# MegaShield_v0_1.net
KiCad netlist of a schematic drawn in EAGLE
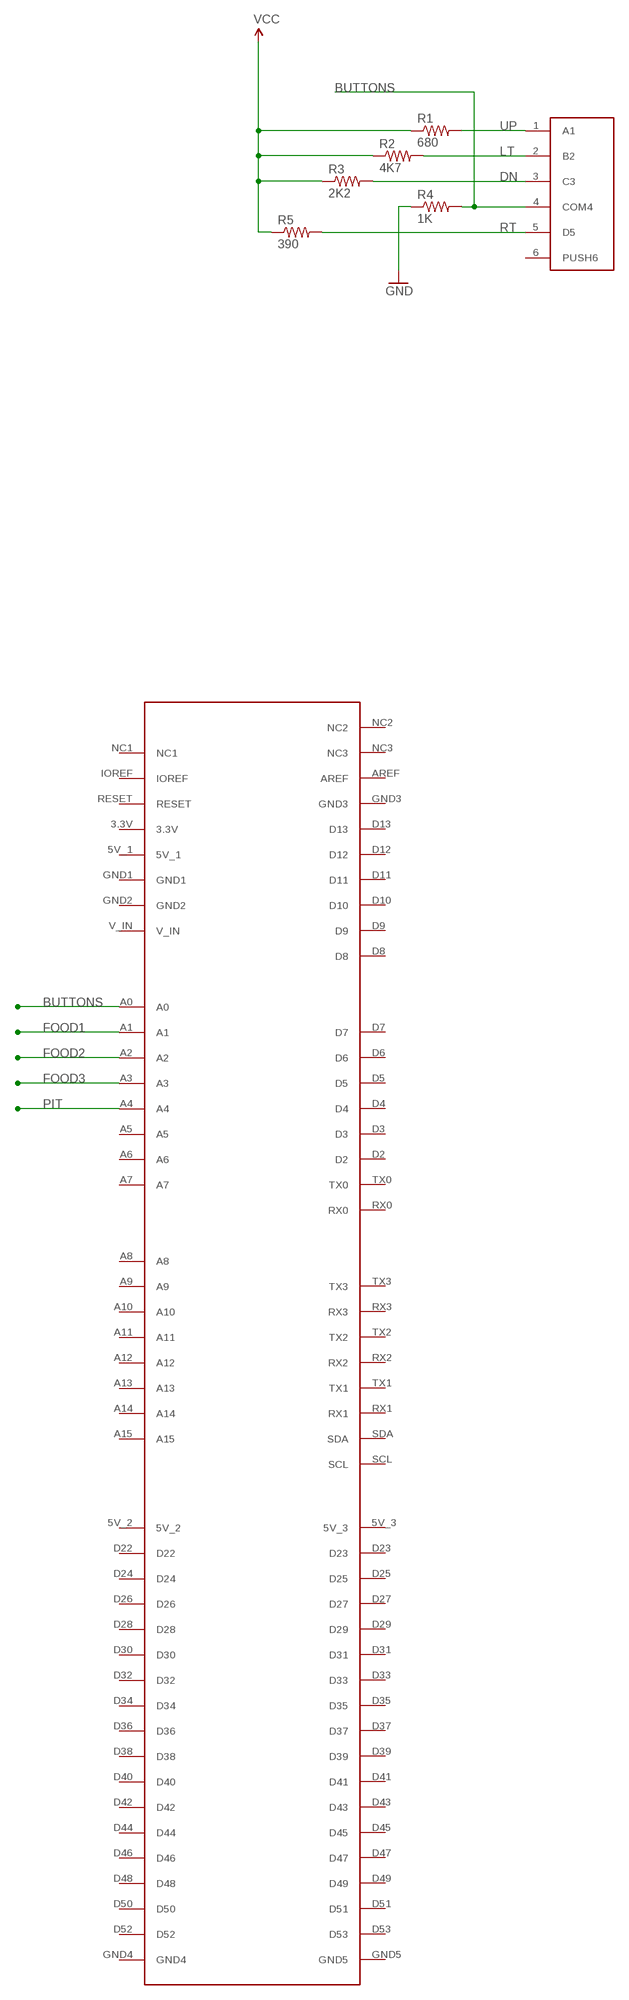
[diagram p0: schematic, sheet 1]

(export (version "E")
  (design (tool "Eeschema 10.0.6"))
  (components
    (comp (ref "R1")
      (value "680")
      (footprint "eagle-import:1206")
      (libsource (lib "eagle-import") (part "RESISTOR1206"))
    )
    (comp (ref "R2")
      (value "4K7")
      (footprint "eagle-import:1206")
      (libsource (lib "eagle-import") (part "RESISTOR1206"))
    )
    (comp (ref "R3")
      (value "2K2")
      (footprint "eagle-import:1206")
      (libsource (lib "eagle-import") (part "RESISTOR1206"))
    )
    (comp (ref "R4")
      (value "1K")
      (footprint "eagle-import:1206")
      (libsource (lib "eagle-import") (part "RESISTOR1206"))
    )
    (comp (ref "R5")
      (value "390")
      (footprint "eagle-import:1206")
      (libsource (lib "eagle-import") (part "RESISTOR1206"))
    )
    (comp (ref "U$1")
      (value "MEGASHILED")
      (footprint "eagle-import:MEGASHIELD")
      (libsource (lib "eagle-import") (part "MEGASHILED"))
    )
    (comp (ref "U$2")
      (value "SKQUAAA010")
      (footprint "eagle-import:SKQUAAA010")
      (libsource (lib "eagle-import") (part "SKQUAAA010"))
    )
  )
  (nets
    (net (code "1") (name "/BUTTONS") (class "Default")
      (node (ref "R4") (pin "2") (pinfunction "2_2") (pintype "passive"))
      (node (ref "U$1") (pin "A0") (pinfunction "A0_A0") (pintype "bidirectional"))
      (node (ref "U$2") (pin "4") (pinfunction "COM4_4") (pintype "bidirectional"))
    )
    (net (code "2") (name "/DN") (class "Default")
      (node (ref "R3") (pin "2") (pinfunction "2_2") (pintype "passive"))
      (node (ref "U$2") (pin "3") (pinfunction "C3_3") (pintype "bidirectional"))
    )
    (net (code "3") (name "/FOOD1") (class "Default")
      (node (ref "U$1") (pin "A1") (pinfunction "A1_A1") (pintype "bidirectional"))
    )
    (net (code "4") (name "/FOOD2") (class "Default")
      (node (ref "U$1") (pin "A2") (pinfunction "A2_A2") (pintype "bidirectional"))
    )
    (net (code "5") (name "/FOOD3") (class "Default")
      (node (ref "U$1") (pin "A3") (pinfunction "A3_A3") (pintype "bidirectional"))
    )
    (net (code "6") (name "/LT") (class "Default")
      (node (ref "R2") (pin "2") (pinfunction "2_2") (pintype "passive"))
      (node (ref "U$2") (pin "2") (pinfunction "B2_2") (pintype "bidirectional"))
    )
    (net (code "7") (name "/PIT") (class "Default")
      (node (ref "U$1") (pin "A4") (pinfunction "A4_A4") (pintype "bidirectional"))
    )
    (net (code "8") (name "/RT") (class "Default")
      (node (ref "R5") (pin "2") (pinfunction "2_2") (pintype "passive"))
      (node (ref "U$2") (pin "5") (pinfunction "D5_5") (pintype "bidirectional"))
    )
    (net (code "9") (name "/UP") (class "Default")
      (node (ref "R1") (pin "2") (pinfunction "2_2") (pintype "passive"))
      (node (ref "U$2") (pin "1") (pinfunction "A1_1") (pintype "bidirectional"))
    )
    (net (code "10") (name "GND") (class "Default")
      (node (ref "R4") (pin "1") (pinfunction "1_1") (pintype "passive"))
    )
    (net (code "11") (name "VCC") (class "Default")
      (node (ref "R1") (pin "1") (pinfunction "1_1") (pintype "passive"))
      (node (ref "R2") (pin "1") (pinfunction "1_1") (pintype "passive"))
      (node (ref "R3") (pin "1") (pinfunction "1_1") (pintype "passive"))
      (node (ref "R5") (pin "1") (pinfunction "1_1") (pintype "passive"))
    )
    (net (code "12") (name "unconnected-(U$1-Pad3.3V)") (class "Default")
      (node (ref "U$1") (pin "3.3V") (pinfunction "3.3V_3.3V") (pintype "bidirectional"))
    )
    (net (code "13") (name "unconnected-(U$1-Pad5V_1)") (class "Default")
      (node (ref "U$1") (pin "5V_1") (pinfunction "5V_1_5V_1") (pintype "bidirectional"))
    )
    (net (code "14") (name "unconnected-(U$1-Pad5V_2)") (class "Default")
      (node (ref "U$1") (pin "5V_2") (pinfunction "5V_2_5V_2") (pintype "bidirectional"))
    )
    (net (code "15") (name "unconnected-(U$1-Pad5V_3)") (class "Default")
      (node (ref "U$1") (pin "5V_3") (pinfunction "5V_3_5V_3") (pintype "bidirectional"))
    )
    (net (code "16") (name "unconnected-(U$1-PadA5)") (class "Default")
      (node (ref "U$1") (pin "A5") (pinfunction "A5_A5") (pintype "bidirectional"))
    )
    (net (code "17") (name "unconnected-(U$1-PadA6)") (class "Default")
      (node (ref "U$1") (pin "A6") (pinfunction "A6_A6") (pintype "bidirectional"))
    )
    (net (code "18") (name "unconnected-(U$1-PadA7)") (class "Default")
      (node (ref "U$1") (pin "A7") (pinfunction "A7_A7") (pintype "bidirectional"))
    )
    (net (code "19") (name "unconnected-(U$1-PadA8)") (class "Default")
      (node (ref "U$1") (pin "A8") (pinfunction "A8_A8") (pintype "bidirectional"))
    )
    (net (code "20") (name "unconnected-(U$1-PadA9)") (class "Default")
      (node (ref "U$1") (pin "A9") (pinfunction "A9_A9") (pintype "bidirectional"))
    )
    (net (code "21") (name "unconnected-(U$1-PadA10)") (class "Default")
      (node (ref "U$1") (pin "A10") (pinfunction "A10_A10") (pintype "bidirectional"))
    )
    (net (code "22") (name "unconnected-(U$1-PadA11)") (class "Default")
      (node (ref "U$1") (pin "A11") (pinfunction "A11_A11") (pintype "bidirectional"))
    )
    (net (code "23") (name "unconnected-(U$1-PadA12)") (class "Default")
      (node (ref "U$1") (pin "A12") (pinfunction "A12_A12") (pintype "bidirectional"))
    )
    (net (code "24") (name "unconnected-(U$1-PadA13)") (class "Default")
      (node (ref "U$1") (pin "A13") (pinfunction "A13_A13") (pintype "bidirectional"))
    )
    (net (code "25") (name "unconnected-(U$1-PadA14)") (class "Default")
      (node (ref "U$1") (pin "A14") (pinfunction "A14_A14") (pintype "bidirectional"))
    )
    (net (code "26") (name "unconnected-(U$1-PadA15)") (class "Default")
      (node (ref "U$1") (pin "A15") (pinfunction "A15_A15") (pintype "bidirectional"))
    )
    (net (code "27") (name "unconnected-(U$1-PadAREF)") (class "Default")
      (node (ref "U$1") (pin "AREF") (pinfunction "AREF_AREF") (pintype "bidirectional"))
    )
    (net (code "28") (name "unconnected-(U$1-PadD2)") (class "Default")
      (node (ref "U$1") (pin "D2") (pinfunction "D2_D2") (pintype "bidirectional"))
    )
    (net (code "29") (name "unconnected-(U$1-PadD3)") (class "Default")
      (node (ref "U$1") (pin "D3") (pinfunction "D3_D3") (pintype "bidirectional"))
    )
    (net (code "30") (name "unconnected-(U$1-PadD4)") (class "Default")
      (node (ref "U$1") (pin "D4") (pinfunction "D4_D4") (pintype "bidirectional"))
    )
    (net (code "31") (name "unconnected-(U$1-PadD5)") (class "Default")
      (node (ref "U$1") (pin "D5") (pinfunction "D5_D5") (pintype "bidirectional"))
    )
    (net (code "32") (name "unconnected-(U$1-PadD6)") (class "Default")
      (node (ref "U$1") (pin "D6") (pinfunction "D6_D6") (pintype "bidirectional"))
    )
    (net (code "33") (name "unconnected-(U$1-PadD7)") (class "Default")
      (node (ref "U$1") (pin "D7") (pinfunction "D7_D7") (pintype "bidirectional"))
    )
    (net (code "34") (name "unconnected-(U$1-PadD8)") (class "Default")
      (node (ref "U$1") (pin "D8") (pinfunction "D8_D8") (pintype "bidirectional"))
    )
    (net (code "35") (name "unconnected-(U$1-PadD9)") (class "Default")
      (node (ref "U$1") (pin "D9") (pinfunction "D9_D9") (pintype "bidirectional"))
    )
    (net (code "36") (name "unconnected-(U$1-PadD10)") (class "Default")
      (node (ref "U$1") (pin "D10") (pinfunction "D10_D10") (pintype "bidirectional"))
    )
    (net (code "37") (name "unconnected-(U$1-PadD11)") (class "Default")
      (node (ref "U$1") (pin "D11") (pinfunction "D11_D11") (pintype "bidirectional"))
    )
    (net (code "38") (name "unconnected-(U$1-PadD12)") (class "Default")
      (node (ref "U$1") (pin "D12") (pinfunction "D12_D12") (pintype "bidirectional"))
    )
    (net (code "39") (name "unconnected-(U$1-PadD13)") (class "Default")
      (node (ref "U$1") (pin "D13") (pinfunction "D13_D13") (pintype "bidirectional"))
    )
    (net (code "40") (name "unconnected-(U$1-PadD22)") (class "Default")
      (node (ref "U$1") (pin "D22") (pinfunction "D22_D22") (pintype "bidirectional"))
    )
    (net (code "41") (name "unconnected-(U$1-PadD23)") (class "Default")
      (node (ref "U$1") (pin "D23") (pinfunction "D23_D23") (pintype "bidirectional"))
    )
    (net (code "42") (name "unconnected-(U$1-PadD24)") (class "Default")
      (node (ref "U$1") (pin "D24") (pinfunction "D24_D24") (pintype "bidirectional"))
    )
    (net (code "43") (name "unconnected-(U$1-PadD25)") (class "Default")
      (node (ref "U$1") (pin "D25") (pinfunction "D25_D25") (pintype "bidirectional"))
    )
    (net (code "44") (name "unconnected-(U$1-PadD26)") (class "Default")
      (node (ref "U$1") (pin "D26") (pinfunction "D26_D26") (pintype "bidirectional"))
    )
    (net (code "45") (name "unconnected-(U$1-PadD27)") (class "Default")
      (node (ref "U$1") (pin "D27") (pinfunction "D27_D27") (pintype "bidirectional"))
    )
    (net (code "46") (name "unconnected-(U$1-PadD28)") (class "Default")
      (node (ref "U$1") (pin "D28") (pinfunction "D28_D28") (pintype "bidirectional"))
    )
    (net (code "47") (name "unconnected-(U$1-PadD29)") (class "Default")
      (node (ref "U$1") (pin "D29") (pinfunction "D29_D29") (pintype "bidirectional"))
    )
    (net (code "48") (name "unconnected-(U$1-PadD30)") (class "Default")
      (node (ref "U$1") (pin "D30") (pinfunction "D30_D30") (pintype "bidirectional"))
    )
    (net (code "49") (name "unconnected-(U$1-PadD31)") (class "Default")
      (node (ref "U$1") (pin "D31") (pinfunction "D31_D31") (pintype "bidirectional"))
    )
    (net (code "50") (name "unconnected-(U$1-PadD32)") (class "Default")
      (node (ref "U$1") (pin "D32") (pinfunction "D32_D32") (pintype "bidirectional"))
    )
    (net (code "51") (name "unconnected-(U$1-PadD33)") (class "Default")
      (node (ref "U$1") (pin "D33") (pinfunction "D33_D33") (pintype "bidirectional"))
    )
    (net (code "52") (name "unconnected-(U$1-PadD34)") (class "Default")
      (node (ref "U$1") (pin "D34") (pinfunction "D34_D34") (pintype "bidirectional"))
    )
    (net (code "53") (name "unconnected-(U$1-PadD35)") (class "Default")
      (node (ref "U$1") (pin "D35") (pinfunction "D35_D35") (pintype "bidirectional"))
    )
    (net (code "54") (name "unconnected-(U$1-PadD36)") (class "Default")
      (node (ref "U$1") (pin "D36") (pinfunction "D36_D36") (pintype "bidirectional"))
    )
    (net (code "55") (name "unconnected-(U$1-PadD37)") (class "Default")
      (node (ref "U$1") (pin "D37") (pinfunction "D37_D37") (pintype "bidirectional"))
    )
    (net (code "56") (name "unconnected-(U$1-PadD38)") (class "Default")
      (node (ref "U$1") (pin "D38") (pinfunction "D38_D38") (pintype "bidirectional"))
    )
    (net (code "57") (name "unconnected-(U$1-PadD39)") (class "Default")
      (node (ref "U$1") (pin "D39") (pinfunction "D39_D39") (pintype "bidirectional"))
    )
    (net (code "58") (name "unconnected-(U$1-PadD40)") (class "Default")
      (node (ref "U$1") (pin "D40") (pinfunction "D40_D40") (pintype "bidirectional"))
    )
    (net (code "59") (name "unconnected-(U$1-PadD41)") (class "Default")
      (node (ref "U$1") (pin "D41") (pinfunction "D41_D41") (pintype "bidirectional"))
    )
    (net (code "60") (name "unconnected-(U$1-PadD42)") (class "Default")
      (node (ref "U$1") (pin "D42") (pinfunction "D42_D42") (pintype "bidirectional"))
    )
    (net (code "61") (name "unconnected-(U$1-PadD43)") (class "Default")
      (node (ref "U$1") (pin "D43") (pinfunction "D43_D43") (pintype "bidirectional"))
    )
    (net (code "62") (name "unconnected-(U$1-PadD44)") (class "Default")
      (node (ref "U$1") (pin "D44") (pinfunction "D44_D44") (pintype "bidirectional"))
    )
    (net (code "63") (name "unconnected-(U$1-PadD45)") (class "Default")
      (node (ref "U$1") (pin "D45") (pinfunction "D45_D45") (pintype "bidirectional"))
    )
    (net (code "64") (name "unconnected-(U$1-PadD46)") (class "Default")
      (node (ref "U$1") (pin "D46") (pinfunction "D46_D46") (pintype "bidirectional"))
    )
    (net (code "65") (name "unconnected-(U$1-PadD47)") (class "Default")
      (node (ref "U$1") (pin "D47") (pinfunction "D47_D47") (pintype "bidirectional"))
    )
    (net (code "66") (name "unconnected-(U$1-PadD48)") (class "Default")
      (node (ref "U$1") (pin "D48") (pinfunction "D48_D48") (pintype "bidirectional"))
    )
    (net (code "67") (name "unconnected-(U$1-PadD49)") (class "Default")
      (node (ref "U$1") (pin "D49") (pinfunction "D49_D49") (pintype "bidirectional"))
    )
    (net (code "68") (name "unconnected-(U$1-PadD50)") (class "Default")
      (node (ref "U$1") (pin "D50") (pinfunction "D50_D50") (pintype "bidirectional"))
    )
    (net (code "69") (name "unconnected-(U$1-PadD51)") (class "Default")
      (node (ref "U$1") (pin "D51") (pinfunction "D51_D51") (pintype "bidirectional"))
    )
    (net (code "70") (name "unconnected-(U$1-PadD52)") (class "Default")
      (node (ref "U$1") (pin "D52") (pinfunction "D52_D52") (pintype "bidirectional"))
    )
    (net (code "71") (name "unconnected-(U$1-PadD53)") (class "Default")
      (node (ref "U$1") (pin "D53") (pinfunction "D53_D53") (pintype "bidirectional"))
    )
    (net (code "72") (name "unconnected-(U$1-PadGND1)") (class "Default")
      (node (ref "U$1") (pin "GND1") (pinfunction "GND1_GND1") (pintype "bidirectional"))
    )
    (net (code "73") (name "unconnected-(U$1-PadGND2)") (class "Default")
      (node (ref "U$1") (pin "GND2") (pinfunction "GND2_GND2") (pintype "bidirectional"))
    )
    (net (code "74") (name "unconnected-(U$1-PadGND3)") (class "Default")
      (node (ref "U$1") (pin "GND3") (pinfunction "GND3_GND3") (pintype "bidirectional"))
    )
    (net (code "75") (name "unconnected-(U$1-PadGND4)") (class "Default")
      (node (ref "U$1") (pin "GND4") (pinfunction "GND4_GND4") (pintype "bidirectional"))
    )
    (net (code "76") (name "unconnected-(U$1-PadGND5)") (class "Default")
      (node (ref "U$1") (pin "GND5") (pinfunction "GND5_GND5") (pintype "bidirectional"))
    )
    (net (code "77") (name "unconnected-(U$1-PadIOREF)") (class "Default")
      (node (ref "U$1") (pin "IOREF") (pinfunction "IOREF_IOREF") (pintype "bidirectional"))
    )
    (net (code "78") (name "unconnected-(U$1-PadNC1)") (class "Default")
      (node (ref "U$1") (pin "NC1") (pinfunction "NC1_NC1") (pintype "bidirectional"))
    )
    (net (code "79") (name "unconnected-(U$1-PadNC2)") (class "Default")
      (node (ref "U$1") (pin "NC2") (pinfunction "NC2_NC2") (pintype "bidirectional"))
    )
    (net (code "80") (name "unconnected-(U$1-PadNC3)") (class "Default")
      (node (ref "U$1") (pin "NC3") (pinfunction "NC3_NC3") (pintype "bidirectional"))
    )
    (net (code "81") (name "unconnected-(U$1-PadRESET)") (class "Default")
      (node (ref "U$1") (pin "RESET") (pinfunction "RESET_RESET") (pintype "bidirectional"))
    )
    (net (code "82") (name "unconnected-(U$1-PadRX0)") (class "Default")
      (node (ref "U$1") (pin "RX0") (pinfunction "RX0_RX0") (pintype "bidirectional"))
    )
    (net (code "83") (name "unconnected-(U$1-PadRX1)") (class "Default")
      (node (ref "U$1") (pin "RX1") (pinfunction "RX1_RX1") (pintype "bidirectional"))
    )
    (net (code "84") (name "unconnected-(U$1-PadRX2)") (class "Default")
      (node (ref "U$1") (pin "RX2") (pinfunction "RX2_RX2") (pintype "bidirectional"))
    )
    (net (code "85") (name "unconnected-(U$1-PadRX3)") (class "Default")
      (node (ref "U$1") (pin "RX3") (pinfunction "RX3_RX3") (pintype "bidirectional"))
    )
    (net (code "86") (name "unconnected-(U$1-PadSCL)") (class "Default")
      (node (ref "U$1") (pin "SCL") (pinfunction "SCL_SCL") (pintype "bidirectional"))
    )
    (net (code "87") (name "unconnected-(U$1-PadSDA)") (class "Default")
      (node (ref "U$1") (pin "SDA") (pinfunction "SDA_SDA") (pintype "bidirectional"))
    )
    (net (code "88") (name "unconnected-(U$1-PadTX0)") (class "Default")
      (node (ref "U$1") (pin "TX0") (pinfunction "TX0_TX0") (pintype "bidirectional"))
    )
    (net (code "89") (name "unconnected-(U$1-PadTX1)") (class "Default")
      (node (ref "U$1") (pin "TX1") (pinfunction "TX1_TX1") (pintype "bidirectional"))
    )
    (net (code "90") (name "unconnected-(U$1-PadTX2)") (class "Default")
      (node (ref "U$1") (pin "TX2") (pinfunction "TX2_TX2") (pintype "bidirectional"))
    )
    (net (code "91") (name "unconnected-(U$1-PadTX3)") (class "Default")
      (node (ref "U$1") (pin "TX3") (pinfunction "TX3_TX3") (pintype "bidirectional"))
    )
    (net (code "92") (name "unconnected-(U$1-PadV_IN)") (class "Default")
      (node (ref "U$1") (pin "V_IN") (pinfunction "V_IN_V_IN") (pintype "bidirectional"))
    )
    (net (code "93") (name "unconnected-(U$2-PUSH6-Pad6)") (class "Default")
      (node (ref "U$2") (pin "6") (pinfunction "PUSH6_6") (pintype "bidirectional"))
    )
  )
)
